# FoodFocus_SchematicDoc.net
KiCad netlist of a schematic drawn in Altium Designer
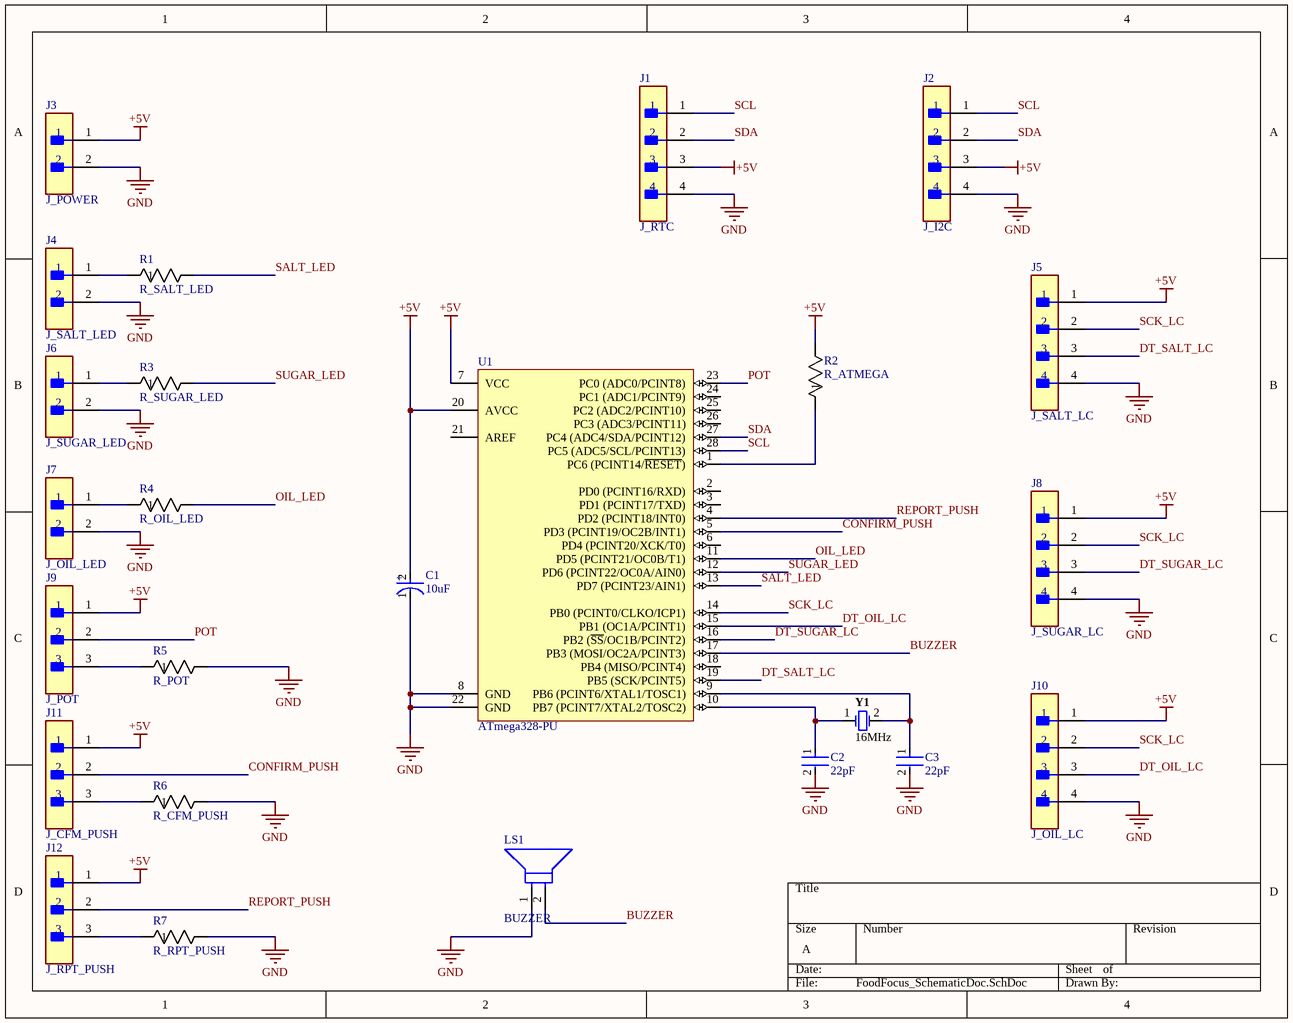
[diagram p0: FoodFocus_SchematicDoc.SchDoc]

(export (version "E")
  (design (tool "Eeschema 10.0.6"))
  (components
    (comp (ref "C1")
      (value "10uF")
      (footprint "FP-RAD-TH-D_5_0_5-L_11_1-MFG")
      (description "Aluminum Electrolytic Capacitors (Radial Lead Type) 10uF ±20% 100V")
      (fields (field (name "VOLTAGE") "100V") (field (name "TOLERANCE") "20%"))
      (libsource (lib "Altium Content Vault") (part "a00bbbee19879c290e62620ae7e47b1"))
    )
    (comp (ref "C2")
      (value "22pF")
      (footprint "FP-VY2472M49Y5UG63V7-MFG")
      (description "Capacitor Ceramic 4700pF ±20% Y5U BULK RADIAL")
      (fields (field (name "TOLERANCE") "20%"))
      (libsource (lib "Altium Content Vault") (part "02cd4be3c70576c341d710602a673aa"))
    )
    (comp (ref "C3")
      (value "22pF")
      (footprint "FP-VY2472M49Y5UG63V7-MFG")
      (description "Capacitor Ceramic 4700pF ±20% Y5U BULK RADIAL")
      (fields (field (name "TOLERANCE") "20%"))
      (libsource (lib "Altium Content Vault") (part "02cd4be3c70576c341d710602a673aa"))
    )
    (comp (ref "J1")
      (value "J_RTC")
      (footprint "FP-35312-0460-MFG")
      (description "CONN HEADER 4POS 2.5MM VERT")
      (libsource (lib "Altium Content Vault") (part "299a8cea1bdcbc3624fe62c390fa72c"))
    )
    (comp (ref "J2")
      (value "J_I2C")
      (footprint "FP-35312-0460-MFG")
      (description "CONN HEADER 4POS 2.5MM VERT")
      (libsource (lib "Altium Content Vault") (part "299a8cea1bdcbc3624fe62c390fa72c"))
    )
    (comp (ref "J3")
      (value "J_POWER")
      (footprint "FP-B2B-XH-A_LF_SN-MFG")
      (description "CONN HEADER VERT 2POS 2.5MM")
      (libsource (lib "Altium Content Vault") (part "3bc925449376181038e59eaffc5286c"))
    )
    (comp (ref "J4")
      (value "J_SALT_LED")
      (footprint "FP-B2B-XH-A_LF_SN-MFG")
      (description "CONN HEADER VERT 2POS 2.5MM")
      (libsource (lib "Altium Content Vault") (part "3bc925449376181038e59eaffc5286c"))
    )
    (comp (ref "J5")
      (value "J_SALT_LC")
      (footprint "FP-35312-0460-MFG")
      (description "CONN HEADER 4POS 2.5MM VERT")
      (libsource (lib "Altium Content Vault") (part "299a8cea1bdcbc3624fe62c390fa72c"))
    )
    (comp (ref "J6")
      (value "J_SUGAR_LED")
      (footprint "FP-B2B-XH-A_LF_SN-MFG")
      (description "CONN HEADER VERT 2POS 2.5MM")
      (libsource (lib "Altium Content Vault") (part "3bc925449376181038e59eaffc5286c"))
    )
    (comp (ref "J7")
      (value "J_OIL_LED")
      (footprint "FP-B2B-XH-A_LF_SN-MFG")
      (description "CONN HEADER VERT 2POS 2.5MM")
      (libsource (lib "Altium Content Vault") (part "3bc925449376181038e59eaffc5286c"))
    )
    (comp (ref "J8")
      (value "J_SUGAR_LC")
      (footprint "FP-35312-0460-MFG")
      (description "CONN HEADER 4POS 2.5MM VERT")
      (libsource (lib "Altium Content Vault") (part "299a8cea1bdcbc3624fe62c390fa72c"))
    )
    (comp (ref "J9")
      (value "J_POT")
      (footprint "FP-B3B-XH-A_LF_SN-MFG")
      (description "CONN HEADER VERT 3POS 2.5MM")
      (libsource (lib "Altium Content Vault") (part "0d3f023dd272f625e17a2be33dea85f"))
    )
    (comp (ref "J10")
      (value "J_OIL_LC")
      (footprint "FP-35312-0460-MFG")
      (description "CONN HEADER 4POS 2.5MM VERT")
      (libsource (lib "Altium Content Vault") (part "299a8cea1bdcbc3624fe62c390fa72c"))
    )
    (comp (ref "J11")
      (value "J_CFM_PUSH")
      (footprint "FP-B3B-XH-A_LF_SN-MFG")
      (description "CONN HEADER VERT 3POS 2.5MM")
      (libsource (lib "Altium Content Vault") (part "0d3f023dd272f625e17a2be33dea85f"))
    )
    (comp (ref "J12")
      (value "J_RPT_PUSH")
      (footprint "FP-B3B-XH-A_LF_SN-MFG")
      (description "CONN HEADER VERT 3POS 2.5MM")
      (libsource (lib "Altium Content Vault") (part "0d3f023dd272f625e17a2be33dea85f"))
    )
    (comp (ref "LS1")
      (value "BUZZER")
      (footprint "FP-MCKPX-G1203A-K4056-MFG")
      (description "MAGNETIC BUZZER AND TRANSDUCER - More Details")
      (fields
        (field (name "MANUFACTURER PART NUMBER") "MCKPX-G1203A-K4056")
        (field (name "MANUFACTURER") "Multicomp Pro")
      )
      (libsource (lib "Altium Content Vault") (part "1973c4b650225fd2ddacaff6b763965"))
    )
    (comp (ref "R1")
      (value "R_SALT_LED")
      (footprint "RES_AC01_VIS")
      (description "AC01000002200JA100 Resistor, 220 Ohm, ± 5%, 1 W, Axial Leaded, Wirewound, General Purpose")
      (fields (field (name "TOLERANCE") "5%"))
      (libsource (lib "Altium Content Vault") (part "AC01000002200JA100"))
    )
    (comp (ref "R2")
      (value "R_ATMEGA")
      (footprint "RES_AC01_VIS")
      (description "AC01000002200JA100 Resistor, 220 Ohm, ± 5%, 1 W, Axial Leaded, Wirewound, General Purpose")
      (fields (field (name "TOLERANCE") "5%"))
      (libsource (lib "Altium Content Vault") (part "AC01000002200JA100"))
    )
    (comp (ref "R3")
      (value "R_SUGAR_LED")
      (footprint "RES_AC01_VIS")
      (description "AC01000002200JA100 Resistor, 220 Ohm, ± 5%, 1 W, Axial Leaded, Wirewound, General Purpose")
      (fields (field (name "TOLERANCE") "5%"))
      (libsource (lib "Altium Content Vault") (part "AC01000002200JA100"))
    )
    (comp (ref "R4")
      (value "R_OIL_LED")
      (footprint "RES_AC01_VIS")
      (description "AC01000002200JA100 Resistor, 220 Ohm, ± 5%, 1 W, Axial Leaded, Wirewound, General Purpose")
      (fields (field (name "TOLERANCE") "5%"))
      (libsource (lib "Altium Content Vault") (part "AC01000002200JA100"))
    )
    (comp (ref "R5")
      (value "R_POT")
      (footprint "RES_AC01_VIS")
      (description "AC01000002200JA100 Resistor, 220 Ohm, ± 5%, 1 W, Axial Leaded, Wirewound, General Purpose")
      (fields (field (name "TOLERANCE") "5%"))
      (libsource (lib "Altium Content Vault") (part "AC01000002200JA100"))
    )
    (comp (ref "R6")
      (value "R_CFM_PUSH")
      (footprint "RES_AC01_VIS")
      (description "AC01000002200JA100 Resistor, 220 Ohm, ± 5%, 1 W, Axial Leaded, Wirewound, General Purpose")
      (fields (field (name "TOLERANCE") "5%"))
      (libsource (lib "Altium Content Vault") (part "AC01000002200JA100"))
    )
    (comp (ref "R7")
      (value "R_RPT_PUSH")
      (footprint "RES_AC01_VIS")
      (description "AC01000002200JA100 Resistor, 220 Ohm, ± 5%, 1 W, Axial Leaded, Wirewound, General Purpose")
      (fields (field (name "TOLERANCE") "5%"))
      (libsource (lib "Altium Content Vault") (part "AC01000002200JA100"))
    )
    (comp (ref "U1")
      (value "ATmega328-PU")
      (footprint "28P3")
      (libsource (lib "Altium Content Vault") (part "MC-8B-ATM48-IL28"))
    )
    (comp (ref "Y1")
      (value "16MHz")
      (footprint "FOX-FOXSLF160-20")
      (description "Resistance Weld Thru-Hole Crystal, 16 MHz, -20 to 70 degC, 2-Pin THD, RoHS, Bulk")
      (fields (field (name "TOLERANCE") "1%"))
      (libsource (lib "Altium Content Vault") (part "XTAL-1-2-2"))
    )
  )
  (nets
    (net (code "1") (name "+5V") (class "Default")
      (node (ref "C1") (pin "2") (pinfunction "A_2") (pintype "passive"))
      (node (ref "J1") (pin "3") (pinfunction "3_3") (pintype "passive"))
      (node (ref "J10") (pin "1") (pinfunction "1_1") (pintype "passive"))
      (node (ref "J11") (pin "1") (pinfunction "1_1") (pintype "passive"))
      (node (ref "J12") (pin "1") (pinfunction "1_1") (pintype "passive"))
      (node (ref "J2") (pin "3") (pinfunction "3_3") (pintype "passive"))
      (node (ref "J3") (pin "1") (pinfunction "1_1") (pintype "passive"))
      (node (ref "J5") (pin "1") (pinfunction "1_1") (pintype "passive"))
      (node (ref "J8") (pin "1") (pinfunction "1_1") (pintype "passive"))
      (node (ref "J9") (pin "1") (pinfunction "1_1") (pintype "passive"))
      (node (ref "R2") (pin "2") (pinfunction "2_2") (pintype "passive"))
      (node (ref "U1") (pin "20") (pinfunction "AVCC_20") (pintype "power_in"))
      (node (ref "U1") (pin "7") (pinfunction "VCC_7") (pintype "power_in"))
    )
    (net (code "2") (name "/BUZZER") (class "Default")
      (node (ref "LS1") (pin "2") (pinfunction "A_2") (pintype "passive"))
      (node (ref "U1") (pin "17") (pinfunction "PB3_(MOSI/OC2A/PCINT3)_17") (pintype "bidirectional"))
    )
    (net (code "3") (name "/CONFIRM_PUSH") (class "Default")
      (node (ref "J11") (pin "2") (pinfunction "2_2") (pintype "passive"))
      (node (ref "U1") (pin "5") (pinfunction "PD3_(PCINT19/OC2B/INT1)_5") (pintype "bidirectional"))
    )
    (net (code "4") (name "/DT_OIL_LC") (class "Default")
      (node (ref "J10") (pin "3") (pinfunction "3_3") (pintype "passive"))
      (node (ref "U1") (pin "15") (pinfunction "PB1_(OC1A/PCINT1)_15") (pintype "bidirectional"))
    )
    (net (code "5") (name "/DT_SALT_LC") (class "Default")
      (node (ref "J5") (pin "3") (pinfunction "3_3") (pintype "passive"))
      (node (ref "U1") (pin "19") (pinfunction "PB5_(SCK/PCINT5)_19") (pintype "bidirectional"))
    )
    (net (code "6") (name "/DT_SUGAR_LC") (class "Default")
      (node (ref "J8") (pin "3") (pinfunction "3_3") (pintype "passive"))
      (node (ref "U1") (pin "16") (pinfunction "PB2_(~{SS}/OC1B/PCINT2)_16") (pintype "bidirectional"))
    )
    (net (code "7") (name "/OIL_LED") (class "Default")
      (node (ref "R4") (pin "2") (pinfunction "2_2") (pintype "passive"))
      (node (ref "U1") (pin "11") (pinfunction "PD5_(PCINT21/OC0B/T1)_11") (pintype "bidirectional"))
    )
    (net (code "8") (name "/POT") (class "Default")
      (node (ref "J9") (pin "2") (pinfunction "2_2") (pintype "passive"))
      (node (ref "U1") (pin "23") (pinfunction "PC0_(ADC0/PCINT8)_23") (pintype "bidirectional"))
    )
    (net (code "9") (name "/REPORT_PUSH") (class "Default")
      (node (ref "J12") (pin "2") (pinfunction "2_2") (pintype "passive"))
      (node (ref "U1") (pin "4") (pinfunction "PD2_(PCINT18/INT0)_4") (pintype "bidirectional"))
    )
    (net (code "10") (name "/SALT_LED") (class "Default")
      (node (ref "R1") (pin "2") (pinfunction "2_2") (pintype "passive"))
      (node (ref "U1") (pin "13") (pinfunction "PD7_(PCINT23/AIN1)_13") (pintype "bidirectional"))
    )
    (net (code "11") (name "/SCK_LC") (class "Default")
      (node (ref "J10") (pin "2") (pinfunction "2_2") (pintype "passive"))
      (node (ref "J5") (pin "2") (pinfunction "2_2") (pintype "passive"))
      (node (ref "J8") (pin "2") (pinfunction "2_2") (pintype "passive"))
      (node (ref "U1") (pin "14") (pinfunction "PB0_(PCINT0/CLKO/ICP1)_14") (pintype "bidirectional"))
    )
    (net (code "12") (name "/SCL") (class "Default")
      (node (ref "J1") (pin "1") (pinfunction "1_1") (pintype "passive"))
      (node (ref "J2") (pin "1") (pinfunction "1_1") (pintype "passive"))
      (node (ref "U1") (pin "28") (pinfunction "PC5_(ADC5/SCL/PCINT13)_28") (pintype "bidirectional"))
    )
    (net (code "13") (name "/SDA") (class "Default")
      (node (ref "J1") (pin "2") (pinfunction "2_2") (pintype "passive"))
      (node (ref "J2") (pin "2") (pinfunction "2_2") (pintype "passive"))
      (node (ref "U1") (pin "27") (pinfunction "PC4_(ADC4/SDA/PCINT12)_27") (pintype "bidirectional"))
    )
    (net (code "14") (name "/SUGAR_LED") (class "Default")
      (node (ref "R3") (pin "2") (pinfunction "2_2") (pintype "passive"))
      (node (ref "U1") (pin "12") (pinfunction "PD6_(PCINT22/OC0A/AIN0)_12") (pintype "bidirectional"))
    )
    (net (code "15") (name "GND") (class "Default")
      (node (ref "C1") (pin "1") (pinfunction "C_1") (pintype "passive"))
      (node (ref "C2") (pin "2") (pinfunction "2_2") (pintype "passive"))
      (node (ref "C3") (pin "2") (pinfunction "2_2") (pintype "passive"))
      (node (ref "J1") (pin "4") (pinfunction "4_4") (pintype "passive"))
      (node (ref "J10") (pin "4") (pinfunction "4_4") (pintype "passive"))
      (node (ref "J2") (pin "4") (pinfunction "4_4") (pintype "passive"))
      (node (ref "J3") (pin "2") (pinfunction "2_2") (pintype "passive"))
      (node (ref "J4") (pin "2") (pinfunction "2_2") (pintype "passive"))
      (node (ref "J5") (pin "4") (pinfunction "4_4") (pintype "passive"))
      (node (ref "J6") (pin "2") (pinfunction "2_2") (pintype "passive"))
      (node (ref "J7") (pin "2") (pinfunction "2_2") (pintype "passive"))
      (node (ref "J8") (pin "4") (pinfunction "4_4") (pintype "passive"))
      (node (ref "LS1") (pin "1") (pinfunction "C_1") (pintype "passive"))
      (node (ref "R5") (pin "2") (pinfunction "2_2") (pintype "passive"))
      (node (ref "R6") (pin "2") (pinfunction "2_2") (pintype "passive"))
      (node (ref "R7") (pin "2") (pinfunction "2_2") (pintype "passive"))
      (node (ref "U1") (pin "22") (pinfunction "GND_22") (pintype "power_in"))
      (node (ref "U1") (pin "8") (pinfunction "GND_8") (pintype "power_in"))
    )
    (net (code "16") (name "Net-(J4-Pad1)") (class "Default")
      (node (ref "J4") (pin "1") (pinfunction "1_1") (pintype "passive"))
      (node (ref "R1") (pin "1") (pinfunction "1_1") (pintype "passive"))
    )
    (net (code "17") (name "Net-(J6-Pad1)") (class "Default")
      (node (ref "J6") (pin "1") (pinfunction "1_1") (pintype "passive"))
      (node (ref "R3") (pin "1") (pinfunction "1_1") (pintype "passive"))
    )
    (net (code "18") (name "Net-(J7-Pad1)") (class "Default")
      (node (ref "J7") (pin "1") (pinfunction "1_1") (pintype "passive"))
      (node (ref "R4") (pin "1") (pinfunction "1_1") (pintype "passive"))
    )
    (net (code "19") (name "Net-(J9-Pad3)") (class "Default")
      (node (ref "J9") (pin "3") (pinfunction "3_3") (pintype "passive"))
      (node (ref "R5") (pin "1") (pinfunction "1_1") (pintype "passive"))
    )
    (net (code "20") (name "Net-(J11-Pad3)") (class "Default")
      (node (ref "J11") (pin "3") (pinfunction "3_3") (pintype "passive"))
      (node (ref "R6") (pin "1") (pinfunction "1_1") (pintype "passive"))
    )
    (net (code "21") (name "Net-(J12-Pad3)") (class "Default")
      (node (ref "J12") (pin "3") (pinfunction "3_3") (pintype "passive"))
      (node (ref "R7") (pin "1") (pinfunction "1_1") (pintype "passive"))
    )
    (net (code "22") (name "Net-(U1-PB6_(PCINT6{slash}XTAL1{slash}TOSC1))") (class "Default")
      (node (ref "C3") (pin "1") (pinfunction "1_1") (pintype "passive"))
      (node (ref "U1") (pin "9") (pinfunction "PB6_(PCINT6/XTAL1/TOSC1)_9") (pintype "bidirectional"))
      (node (ref "Y1") (pin "2") (pinfunction "2_2") (pintype "passive"))
    )
    (net (code "23") (name "Net-(U1-PB7_(PCINT7{slash}XTAL2{slash}TOSC2))") (class "Default")
      (node (ref "C2") (pin "1") (pinfunction "1_1") (pintype "passive"))
      (node (ref "U1") (pin "10") (pinfunction "PB7_(PCINT7/XTAL2/TOSC2)_10") (pintype "bidirectional"))
      (node (ref "Y1") (pin "1") (pinfunction "1_1") (pintype "passive"))
    )
    (net (code "24") (name "Net-(U1-PC6_(PCINT14{slash}~{RESET}))") (class "Default")
      (node (ref "R2") (pin "1") (pinfunction "1_1") (pintype "passive"))
      (node (ref "U1") (pin "1") (pinfunction "PC6_(PCINT14/~{RESET})_1") (pintype "bidirectional"))
    )
    (net (code "25") (name "unconnected-(U1-AREF-Pad21)") (class "Default")
      (node (ref "U1") (pin "21") (pinfunction "AREF_21") (pintype "power_in"))
    )
    (net (code "26") (name "unconnected-(U1-PB4_(MISO{slash}PCINT4)-Pad18)") (class "Default")
      (node (ref "U1") (pin "18") (pinfunction "PB4_(MISO/PCINT4)_18") (pintype "bidirectional"))
    )
    (net (code "27") (name "unconnected-(U1-PC1_(ADC1{slash}PCINT9)-Pad24)") (class "Default")
      (node (ref "U1") (pin "24") (pinfunction "PC1_(ADC1/PCINT9)_24") (pintype "bidirectional"))
    )
    (net (code "28") (name "unconnected-(U1-PC2_(ADC2{slash}PCINT10)-Pad25)") (class "Default")
      (node (ref "U1") (pin "25") (pinfunction "PC2_(ADC2/PCINT10)_25") (pintype "bidirectional"))
    )
    (net (code "29") (name "unconnected-(U1-PC3_(ADC3{slash}PCINT11)-Pad26)") (class "Default")
      (node (ref "U1") (pin "26") (pinfunction "PC3_(ADC3/PCINT11)_26") (pintype "bidirectional"))
    )
    (net (code "30") (name "unconnected-(U1-PD0_(PCINT16{slash}RXD)-Pad2)") (class "Default")
      (node (ref "U1") (pin "2") (pinfunction "PD0_(PCINT16/RXD)_2") (pintype "bidirectional"))
    )
    (net (code "31") (name "unconnected-(U1-PD1_(PCINT17{slash}TXD)-Pad3)") (class "Default")
      (node (ref "U1") (pin "3") (pinfunction "PD1_(PCINT17/TXD)_3") (pintype "bidirectional"))
    )
    (net (code "32") (name "unconnected-(U1-PD4_(PCINT20{slash}XCK{slash}T0)-Pad6)") (class "Default")
      (node (ref "U1") (pin "6") (pinfunction "PD4_(PCINT20/XCK/T0)_6") (pintype "bidirectional"))
    )
  )
)
